# Base.net
KiCad netlist of a schematic drawn in EAGLE
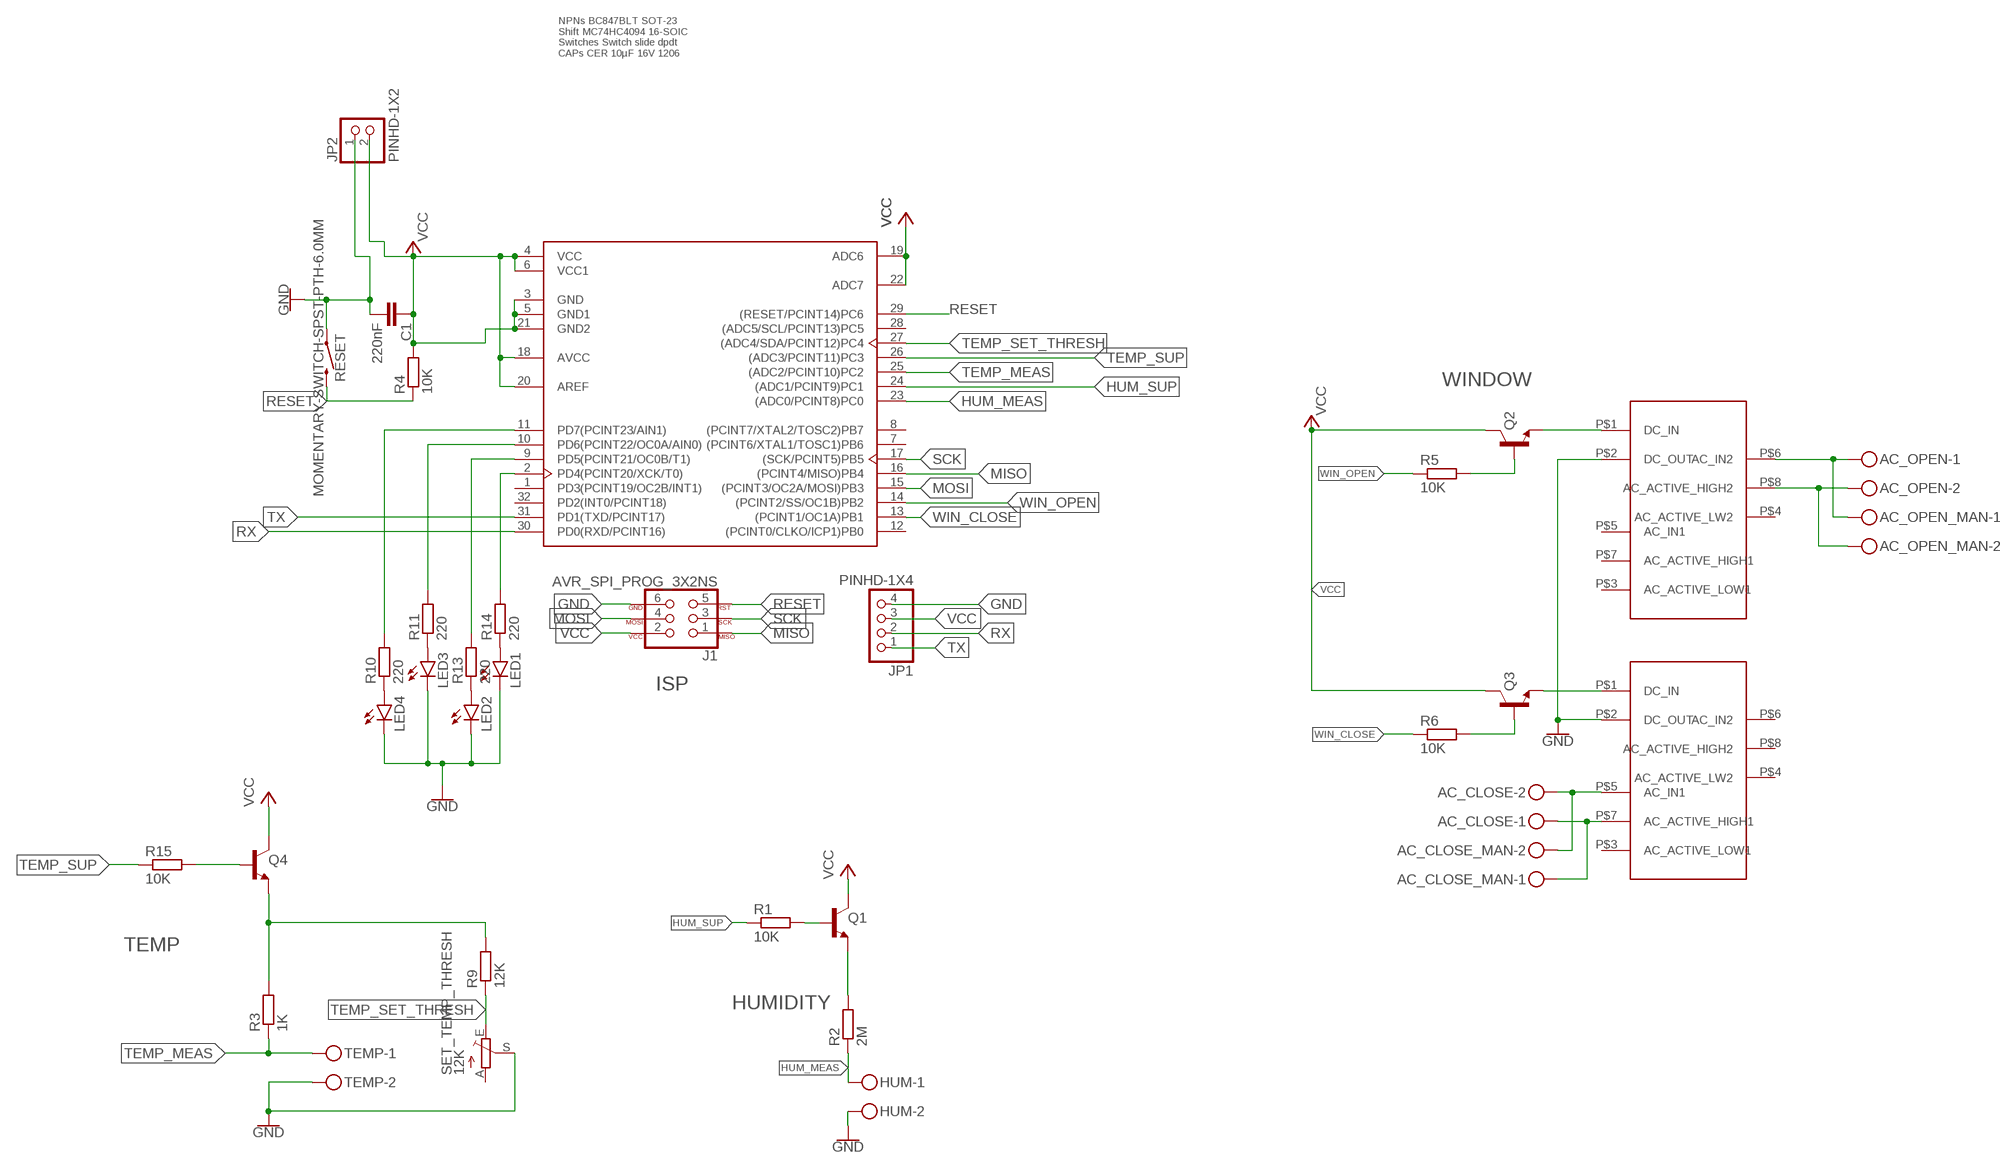
[diagram p0: schematic, sheet 1]

(export (version "E")
  (design (tool "Eeschema 10.0.6"))
  (components
    (comp (ref "AC_CLOSE")
      (value "MKDSN1,5/2-5,08")
      (footprint "eagle-import:MKDSN1,5_2-5,08")
      (libsource (lib "eagle-import") (part "MKDSN1,5/2-5,08"))
    )
    (comp (ref "AC_CLOSE_MAN")
      (value "MKDSN1,5/2-5,08")
      (footprint "eagle-import:MKDSN1,5_2-5,08")
      (libsource (lib "eagle-import") (part "MKDSN1,5/2-5,08"))
    )
    (comp (ref "AC_OPEN")
      (value "MKDSN1,5/2-5,08")
      (footprint "eagle-import:MKDSN1,5_2-5,08")
      (libsource (lib "eagle-import") (part "MKDSN1,5/2-5,08"))
    )
    (comp (ref "AC_OPEN_MAN")
      (value "MKDSN1,5/2-5,08")
      (footprint "eagle-import:MKDSN1,5_2-5,08")
      (libsource (lib "eagle-import") (part "MKDSN1,5/2-5,08"))
    )
    (comp (ref "C1")
      (value "220nF")
      (footprint "eagle-import:C0805")
      (libsource (lib "eagle-import") (part "C-EUC0805"))
    )
    (comp (ref "HUM")
      (value "MKDSN1,5/2-5,08")
      (footprint "eagle-import:MKDSN1,5_2-5,08")
      (libsource (lib "eagle-import") (part "MKDSN1,5/2-5,08"))
    )
    (comp (ref "J1")
      (value "AVR_SPI_PROG_3X2NS")
      (footprint "eagle-import:2X3-NS")
      (libsource (lib "eagle-import") (part "AVR_SPI_PROG_3X2NS"))
    )
    (comp (ref "JP1")
      (value "PINHD-1X4")
      (footprint "eagle-import:1X04")
      (libsource (lib "eagle-import") (part "PINHD-1X4"))
    )
    (comp (ref "JP2")
      (value "PINHD-1X2")
      (footprint "eagle-import:1X02")
      (libsource (lib "eagle-import") (part "PINHD-1X2"))
    )
    (comp (ref "LED1")
      (value "LEDSMT1206")
      (footprint "eagle-import:1206")
      (libsource (lib "eagle-import") (part "LEDSMT1206"))
    )
    (comp (ref "LED2")
      (value "LEDSMT1206")
      (footprint "eagle-import:1206")
      (libsource (lib "eagle-import") (part "LEDSMT1206"))
    )
    (comp (ref "LED3")
      (value "LEDSMT1206")
      (footprint "eagle-import:1206")
      (libsource (lib "eagle-import") (part "LEDSMT1206"))
    )
    (comp (ref "LED4")
      (value "LEDSMT1206")
      (footprint "eagle-import:1206")
      (libsource (lib "eagle-import") (part "LEDSMT1206"))
    )
    (comp (ref "Q1")
      (value "BD139")
      (footprint "eagle-import:SOT23-BEC")
      (libsource (lib "eagle-import") (part "-NPN-SOT23-BECBC847BLT1"))
    )
    (comp (ref "Q2")
      (value "BD139")
      (footprint "eagle-import:SOT23-BEC")
      (libsource (lib "eagle-import") (part "-NPN-SOT23-BECBC847BLT1"))
    )
    (comp (ref "Q3")
      (value "BD139")
      (footprint "eagle-import:SOT23-BEC")
      (libsource (lib "eagle-import") (part "-NPN-SOT23-BECBC847BLT1"))
    )
    (comp (ref "Q4")
      (value "BD139")
      (footprint "eagle-import:SOT23-BEC")
      (libsource (lib "eagle-import") (part "-NPN-SOT23-BECBC847BLT1"))
    )
    (comp (ref "R1")
      (value "10K")
      (footprint "eagle-import:R1206")
      (libsource (lib "eagle-import") (part "R-EU_R1206"))
    )
    (comp (ref "R2")
      (value "2M")
      (footprint "eagle-import:R1206")
      (libsource (lib "eagle-import") (part "R-EU_R1206"))
    )
    (comp (ref "R3")
      (value "1K")
      (footprint "eagle-import:R1206")
      (libsource (lib "eagle-import") (part "R-EU_R1206"))
    )
    (comp (ref "R4")
      (value "10K")
      (footprint "eagle-import:R1206")
      (libsource (lib "eagle-import") (part "R-EU_R1206"))
    )
    (comp (ref "R5")
      (value "10K")
      (footprint "eagle-import:R1206")
      (libsource (lib "eagle-import") (part "R-EU_R1206"))
    )
    (comp (ref "R6")
      (value "10K")
      (footprint "eagle-import:R1206")
      (libsource (lib "eagle-import") (part "R-EU_R1206"))
    )
    (comp (ref "R9")
      (value "12K")
      (footprint "eagle-import:R1206")
      (libsource (lib "eagle-import") (part "R-EU_R1206"))
    )
    (comp (ref "R10")
      (value "220")
      (footprint "eagle-import:R1206")
      (libsource (lib "eagle-import") (part "R-EU_R1206"))
    )
    (comp (ref "R11")
      (value "220")
      (footprint "eagle-import:R1206")
      (libsource (lib "eagle-import") (part "R-EU_R1206"))
    )
    (comp (ref "R13")
      (value "220")
      (footprint "eagle-import:R1206")
      (libsource (lib "eagle-import") (part "R-EU_R1206"))
    )
    (comp (ref "R14")
      (value "220")
      (footprint "eagle-import:R1206")
      (libsource (lib "eagle-import") (part "R-EU_R1206"))
    )
    (comp (ref "R15")
      (value "10K")
      (footprint "eagle-import:R1206")
      (libsource (lib "eagle-import") (part "R-EU_R1206"))
    )
    (comp (ref "RESET")
      (value "MOMENTARY-SWITCH-SPST-PTH-6.0MM")
      (footprint "eagle-import:TACTILE_SWITCH_PTH_6.0MM")
      (libsource (lib "eagle-import") (part "MOMENTARY-SWITCH-SPST-PTH-6.0MM"))
    )
    (comp (ref "SET_TEMP_THRESH")
      (value "12K")
      (footprint "eagle-import:LI15")
      (libsource (lib "eagle-import") (part "TRIM_EU-LI15"))
    )
    (comp (ref "TEMP")
      (value "MKDSN1,5/2-5,08")
      (footprint "eagle-import:MKDSN1,5_2-5,08")
      (libsource (lib "eagle-import") (part "MKDSN1,5/2-5,08"))
    )
    (comp (ref "U$1")
      (value "RELAIS_EAG")
      (footprint "eagle-import:REALAIS_EAG")
      (libsource (lib "eagle-import") (part "RELAIS_EAG"))
    )
    (comp (ref "U$2")
      (value "RELAIS_EAG")
      (footprint "eagle-import:REALAIS_EAG")
      (libsource (lib "eagle-import") (part "RELAIS_EAG"))
    )
    (comp (ref "U2")
      (value "ATMEGA328P-AU")
      (footprint "eagle-import:TQFP-32")
      (fields
        (field (name "DIGIKEY_PART_NUMBER") "ATMEGA328P-AU-ND")
        (field (name "MANUFACTURER") "Microchip Technology")
        (field (name "CREATED_BY") "PCBLayout.com")
      )
      (libsource (lib "eagle-import") (part "ATMEGA328P-AU"))
    )
  )
  (nets
    (net (code "1") (name "GND") (class "Default")
      (node (ref "C1") (pin "2") (pinfunction "2_2") (pintype "passive"))
      (node (ref "HUM") (pin "2") (pinfunction "KL_2") (pintype "passive"))
      (node (ref "J1") (pin "6") (pinfunction "6_6") (pintype "passive"))
      (node (ref "JP1") (pin "4") (pinfunction "4_4") (pintype "passive"))
      (node (ref "JP2") (pin "1") (pinfunction "1_1") (pintype "passive"))
      (node (ref "LED1") (pin "C") (pinfunction "C_C") (pintype "passive"))
      (node (ref "LED2") (pin "C") (pinfunction "C_C") (pintype "passive"))
      (node (ref "LED3") (pin "C") (pinfunction "C_C") (pintype "passive"))
      (node (ref "LED4") (pin "C") (pinfunction "C_C") (pintype "passive"))
      (node (ref "RESET") (pin "1") (pinfunction "1_1") (pintype "passive"))
      (node (ref "SET_TEMP_THRESH") (pin "S") (pinfunction "S_S") (pintype "passive"))
      (node (ref "TEMP") (pin "2") (pinfunction "KL_2") (pintype "passive"))
      (node (ref "U$1") (pin "P$2") (pinfunction "DC_OUT_P$2") (pintype "bidirectional"))
      (node (ref "U$2") (pin "P$2") (pinfunction "DC_OUT_P$2") (pintype "bidirectional"))
    )
    (net (code "2") (name "HUM_MEAS") (class "Default")
      (node (ref "HUM") (pin "1") (pinfunction "KL_1") (pintype "passive"))
      (node (ref "R2") (pin "1") (pinfunction "1_1") (pintype "passive"))
      (node (ref "U2") (pin "23") (pinfunction "(ADC0/PCINT8)PC0_23") (pintype "bidirectional"))
    )
    (net (code "3") (name "HUM_SUP") (class "Default")
      (node (ref "R1") (pin "1") (pinfunction "1_1") (pintype "passive"))
      (node (ref "U2") (pin "24") (pinfunction "(ADC1/PCINT9)PC1_24") (pintype "bidirectional"))
    )
    (net (code "4") (name "MISO") (class "Default")
      (node (ref "J1") (pin "1") (pinfunction "1_1") (pintype "passive"))
      (node (ref "U2") (pin "16") (pinfunction "(PCINT4/MISO)PB4_16") (pintype "bidirectional"))
    )
    (net (code "5") (name "MOSI") (class "Default")
      (node (ref "J1") (pin "4") (pinfunction "4_4") (pintype "passive"))
      (node (ref "U2") (pin "15") (pinfunction "(PCINT3/OC2A/MOSI)PB3_15") (pintype "bidirectional"))
    )
    (net (code "6") (name "Net-(AC_CLOSEA-KL)") (class "Default")
      (node (ref "AC_CLOSE") (pin "1") (pinfunction "KL_1") (pintype "passive"))
      (node (ref "AC_CLOSE_MAN") (pin "1") (pinfunction "KL_1") (pintype "passive"))
      (node (ref "U$2") (pin "P$7") (pinfunction "AC_ACTIVE_HIGH1_P$7") (pintype "bidirectional"))
    )
    (net (code "7") (name "Net-(AC_CLOSEB-KL)") (class "Default")
      (node (ref "AC_CLOSE") (pin "2") (pinfunction "KL_2") (pintype "passive"))
      (node (ref "AC_CLOSE_MAN") (pin "2") (pinfunction "KL_2") (pintype "passive"))
      (node (ref "U$2") (pin "P$5") (pinfunction "AC_IN1_P$5") (pintype "bidirectional"))
    )
    (net (code "8") (name "Net-(AC_OPENA-KL)") (class "Default")
      (node (ref "AC_OPEN") (pin "1") (pinfunction "KL_1") (pintype "passive"))
      (node (ref "AC_OPEN_MAN") (pin "1") (pinfunction "KL_1") (pintype "passive"))
      (node (ref "U$1") (pin "P$6") (pinfunction "AC_IN2_P$6") (pintype "bidirectional"))
    )
    (net (code "9") (name "Net-(AC_OPENB-KL)") (class "Default")
      (node (ref "AC_OPEN") (pin "2") (pinfunction "KL_2") (pintype "passive"))
      (node (ref "AC_OPEN_MAN") (pin "2") (pinfunction "KL_2") (pintype "passive"))
      (node (ref "U$1") (pin "P$8") (pinfunction "AC_ACTIVE_HIGH2_P$8") (pintype "bidirectional"))
    )
    (net (code "10") (name "Net-(LED1-PadA)") (class "Default")
      (node (ref "LED1") (pin "A") (pinfunction "A_A") (pintype "passive"))
      (node (ref "R14") (pin "1") (pinfunction "1_1") (pintype "passive"))
    )
    (net (code "11") (name "Net-(LED2-PadA)") (class "Default")
      (node (ref "LED2") (pin "A") (pinfunction "A_A") (pintype "passive"))
      (node (ref "R13") (pin "1") (pinfunction "1_1") (pintype "passive"))
    )
    (net (code "12") (name "Net-(LED3-PadA)") (class "Default")
      (node (ref "LED3") (pin "A") (pinfunction "A_A") (pintype "passive"))
      (node (ref "R11") (pin "1") (pinfunction "1_1") (pintype "passive"))
    )
    (net (code "13") (name "Net-(LED4-PadA)") (class "Default")
      (node (ref "LED4") (pin "A") (pinfunction "A_A") (pintype "passive"))
      (node (ref "R10") (pin "1") (pinfunction "1_1") (pintype "passive"))
    )
    (net (code "14") (name "Net-(Q1-PadB)") (class "Default")
      (node (ref "Q1") (pin "B") (pinfunction "B_B") (pintype "passive"))
      (node (ref "R1") (pin "2") (pinfunction "2_2") (pintype "passive"))
    )
    (net (code "15") (name "Net-(Q1-PadE)") (class "Default")
      (node (ref "Q1") (pin "E") (pinfunction "E_E") (pintype "passive"))
      (node (ref "R2") (pin "2") (pinfunction "2_2") (pintype "passive"))
    )
    (net (code "16") (name "Net-(Q2-PadB)") (class "Default")
      (node (ref "Q2") (pin "B") (pinfunction "B_B") (pintype "passive"))
      (node (ref "R5") (pin "2") (pinfunction "2_2") (pintype "passive"))
    )
    (net (code "17") (name "Net-(Q3-PadB)") (class "Default")
      (node (ref "Q3") (pin "B") (pinfunction "B_B") (pintype "passive"))
      (node (ref "R6") (pin "2") (pinfunction "2_2") (pintype "passive"))
    )
    (net (code "18") (name "Net-(Q4-PadB)") (class "Default")
      (node (ref "Q4") (pin "B") (pinfunction "B_B") (pintype "passive"))
      (node (ref "R15") (pin "2") (pinfunction "2_2") (pintype "passive"))
    )
    (net (code "19") (name "Net-(Q4-PadE)") (class "Default")
      (node (ref "Q4") (pin "E") (pinfunction "E_E") (pintype "passive"))
      (node (ref "R3") (pin "2") (pinfunction "2_2") (pintype "passive"))
      (node (ref "R9") (pin "2") (pinfunction "2_2") (pintype "passive"))
    )
    (net (code "20") (name "Net-(U$1-DC_IN)") (class "Default")
      (node (ref "Q2") (pin "E") (pinfunction "E_E") (pintype "passive"))
      (node (ref "U$1") (pin "P$1") (pinfunction "DC_IN_P$1") (pintype "bidirectional"))
    )
    (net (code "21") (name "Net-(U$2-DC_IN)") (class "Default")
      (node (ref "Q3") (pin "E") (pinfunction "E_E") (pintype "passive"))
      (node (ref "U$2") (pin "P$1") (pinfunction "DC_IN_P$1") (pintype "bidirectional"))
    )
    (net (code "22") (name "Net-(U2-PD4(PCINT20{slash}XCK{slash}T0))") (class "Default")
      (node (ref "R14") (pin "2") (pinfunction "2_2") (pintype "passive"))
      (node (ref "U2") (pin "2") (pinfunction "PD4(PCINT20/XCK/T0)_2") (pintype "bidirectional"))
    )
    (net (code "23") (name "Net-(U2-PD5(PCINT21{slash}OC0B{slash}T1))") (class "Default")
      (node (ref "R13") (pin "2") (pinfunction "2_2") (pintype "passive"))
      (node (ref "U2") (pin "9") (pinfunction "PD5(PCINT21/OC0B/T1)_9") (pintype "bidirectional"))
    )
    (net (code "24") (name "Net-(U2-PD6(PCINT22{slash}OC0A{slash}AIN0))") (class "Default")
      (node (ref "R11") (pin "2") (pinfunction "2_2") (pintype "passive"))
      (node (ref "U2") (pin "10") (pinfunction "PD6(PCINT22/OC0A/AIN0)_10") (pintype "bidirectional"))
    )
    (net (code "25") (name "Net-(U2-PD7(PCINT23{slash}AIN1))") (class "Default")
      (node (ref "R10") (pin "2") (pinfunction "2_2") (pintype "passive"))
      (node (ref "U2") (pin "11") (pinfunction "PD7(PCINT23/AIN1)_11") (pintype "bidirectional"))
    )
    (net (code "26") (name "RESET") (class "Default")
      (node (ref "J1") (pin "5") (pinfunction "5_5") (pintype "passive"))
      (node (ref "R4") (pin "1") (pinfunction "1_1") (pintype "passive"))
      (node (ref "RESET") (pin "3") (pinfunction "2_3") (pintype "passive"))
      (node (ref "U2") (pin "29") (pinfunction "(RESET/PCINT14)PC6_29") (pintype "bidirectional"))
    )
    (net (code "27") (name "RX") (class "Default")
      (node (ref "JP1") (pin "2") (pinfunction "2_2") (pintype "passive"))
      (node (ref "U2") (pin "30") (pinfunction "PD0(RXD/PCINT16)_30") (pintype "bidirectional"))
    )
    (net (code "28") (name "SCK") (class "Default")
      (node (ref "J1") (pin "3") (pinfunction "3_3") (pintype "passive"))
      (node (ref "U2") (pin "17") (pinfunction "(SCK/PCINT5)PB5_17") (pintype "bidirectional"))
    )
    (net (code "29") (name "TEMP_MEAS") (class "Default")
      (node (ref "R3") (pin "1") (pinfunction "1_1") (pintype "passive"))
      (node (ref "TEMP") (pin "1") (pinfunction "KL_1") (pintype "passive"))
      (node (ref "U2") (pin "25") (pinfunction "(ADC2/PCINT10)PC2_25") (pintype "bidirectional"))
    )
    (net (code "30") (name "TEMP_SET_THRESH") (class "Default")
      (node (ref "R9") (pin "1") (pinfunction "1_1") (pintype "passive"))
      (node (ref "SET_TEMP_THRESH") (pin "E") (pinfunction "E_E") (pintype "passive"))
      (node (ref "U2") (pin "27") (pinfunction "(ADC4/SDA/PCINT12)PC4_27") (pintype "bidirectional"))
    )
    (net (code "31") (name "TEMP_SUP") (class "Default")
      (node (ref "R15") (pin "1") (pinfunction "1_1") (pintype "passive"))
      (node (ref "U2") (pin "26") (pinfunction "(ADC3/PCINT11)PC3_26") (pintype "bidirectional"))
    )
    (net (code "32") (name "TX") (class "Default")
      (node (ref "JP1") (pin "1") (pinfunction "1_1") (pintype "passive"))
      (node (ref "U2") (pin "31") (pinfunction "PD1(TXD/PCINT17)_31") (pintype "bidirectional"))
    )
    (net (code "33") (name "VCC") (class "Default")
      (node (ref "C1") (pin "1") (pinfunction "1_1") (pintype "passive"))
      (node (ref "J1") (pin "2") (pinfunction "2_2") (pintype "passive"))
      (node (ref "JP1") (pin "3") (pinfunction "3_3") (pintype "passive"))
      (node (ref "JP2") (pin "2") (pinfunction "2_2") (pintype "passive"))
      (node (ref "Q1") (pin "C") (pinfunction "C_C") (pintype "passive"))
      (node (ref "Q2") (pin "C") (pinfunction "C_C") (pintype "passive"))
      (node (ref "Q3") (pin "C") (pinfunction "C_C") (pintype "passive"))
      (node (ref "Q4") (pin "C") (pinfunction "C_C") (pintype "passive"))
      (node (ref "R4") (pin "2") (pinfunction "2_2") (pintype "passive"))
      (node (ref "U2") (pin "18") (pinfunction "AVCC_18") (pintype "power_in"))
      (node (ref "U2") (pin "19") (pinfunction "ADC6_19") (pintype "input"))
      (node (ref "U2") (pin "20") (pinfunction "AREF_20") (pintype "power_in"))
      (node (ref "U2") (pin "21") (pinfunction "GND2_21") (pintype "power_in"))
      (node (ref "U2") (pin "22") (pinfunction "ADC7_22") (pintype "input"))
      (node (ref "U2") (pin "3") (pinfunction "GND_3") (pintype "power_in"))
      (node (ref "U2") (pin "4") (pinfunction "VCC_4") (pintype "power_in"))
      (node (ref "U2") (pin "5") (pinfunction "GND1_5") (pintype "power_in"))
      (node (ref "U2") (pin "6") (pinfunction "VCC1_6") (pintype "power_in"))
    )
    (net (code "34") (name "WIN_CLOSE") (class "Default")
      (node (ref "R6") (pin "1") (pinfunction "1_1") (pintype "passive"))
      (node (ref "U2") (pin "13") (pinfunction "(PCINT1/OC1A)PB1_13") (pintype "bidirectional"))
    )
    (net (code "35") (name "WIN_OPEN") (class "Default")
      (node (ref "R5") (pin "1") (pinfunction "1_1") (pintype "passive"))
      (node (ref "U2") (pin "14") (pinfunction "(PCINT2/SS/OC1B)PB2_14") (pintype "bidirectional"))
    )
    (net (code "36") (name "unconnected-(SET_TEMP_THRESH-PadA)") (class "Default")
      (node (ref "SET_TEMP_THRESH") (pin "A") (pinfunction "A_A") (pintype "passive"))
    )
    (net (code "37") (name "unconnected-(U$1-AC_ACTIVE_HIGH1-PadP$7)") (class "Default")
      (node (ref "U$1") (pin "P$7") (pinfunction "AC_ACTIVE_HIGH1_P$7") (pintype "bidirectional"))
    )
    (net (code "38") (name "unconnected-(U$1-AC_ACTIVE_LOW1-PadP$3)") (class "Default")
      (node (ref "U$1") (pin "P$3") (pinfunction "AC_ACTIVE_LOW1_P$3") (pintype "bidirectional"))
    )
    (net (code "39") (name "unconnected-(U$1-AC_ACTIVE_LW2-PadP$4)") (class "Default")
      (node (ref "U$1") (pin "P$4") (pinfunction "AC_ACTIVE_LW2_P$4") (pintype "bidirectional"))
    )
    (net (code "40") (name "unconnected-(U$1-AC_IN1-PadP$5)") (class "Default")
      (node (ref "U$1") (pin "P$5") (pinfunction "AC_IN1_P$5") (pintype "bidirectional"))
    )
    (net (code "41") (name "unconnected-(U$2-AC_ACTIVE_HIGH2-PadP$8)") (class "Default")
      (node (ref "U$2") (pin "P$8") (pinfunction "AC_ACTIVE_HIGH2_P$8") (pintype "bidirectional"))
    )
    (net (code "42") (name "unconnected-(U$2-AC_ACTIVE_LOW1-PadP$3)") (class "Default")
      (node (ref "U$2") (pin "P$3") (pinfunction "AC_ACTIVE_LOW1_P$3") (pintype "bidirectional"))
    )
    (net (code "43") (name "unconnected-(U$2-AC_ACTIVE_LW2-PadP$4)") (class "Default")
      (node (ref "U$2") (pin "P$4") (pinfunction "AC_ACTIVE_LW2_P$4") (pintype "bidirectional"))
    )
    (net (code "44") (name "unconnected-(U$2-AC_IN2-PadP$6)") (class "Default")
      (node (ref "U$2") (pin "P$6") (pinfunction "AC_IN2_P$6") (pintype "bidirectional"))
    )
    (net (code "45") (name "unconnected-(U2-(ADC5{slash}SCL{slash}PCINT13)PC5-Pad28)") (class "Default")
      (node (ref "U2") (pin "28") (pinfunction "(ADC5/SCL/PCINT13)PC5_28") (pintype "bidirectional"))
    )
    (net (code "46") (name "unconnected-(U2-(PCINT0{slash}CLKO{slash}ICP1)PB0-Pad12)") (class "Default")
      (node (ref "U2") (pin "12") (pinfunction "(PCINT0/CLKO/ICP1)PB0_12") (pintype "bidirectional"))
    )
    (net (code "47") (name "unconnected-(U2-(PCINT6{slash}XTAL1{slash}TOSC1)PB6-Pad7)") (class "Default")
      (node (ref "U2") (pin "7") (pinfunction "(PCINT6/XTAL1/TOSC1)PB6_7") (pintype "bidirectional"))
    )
    (net (code "48") (name "unconnected-(U2-(PCINT7{slash}XTAL2{slash}TOSC2)PB7-Pad8)") (class "Default")
      (node (ref "U2") (pin "8") (pinfunction "(PCINT7/XTAL2/TOSC2)PB7_8") (pintype "bidirectional"))
    )
    (net (code "49") (name "unconnected-(U2-PD2(INT0{slash}PCINT18)-Pad32)") (class "Default")
      (node (ref "U2") (pin "32") (pinfunction "PD2(INT0/PCINT18)_32") (pintype "bidirectional"))
    )
    (net (code "50") (name "unconnected-(U2-PD3(PCINT19{slash}OC2B{slash}INT1)-Pad1)") (class "Default")
      (node (ref "U2") (pin "1") (pinfunction "PD3(PCINT19/OC2B/INT1)_1") (pintype "bidirectional"))
    )
  )
)
